# 15P1D_EDA.net
KiCad netlist of a schematic drawn in EasyEDA Pro
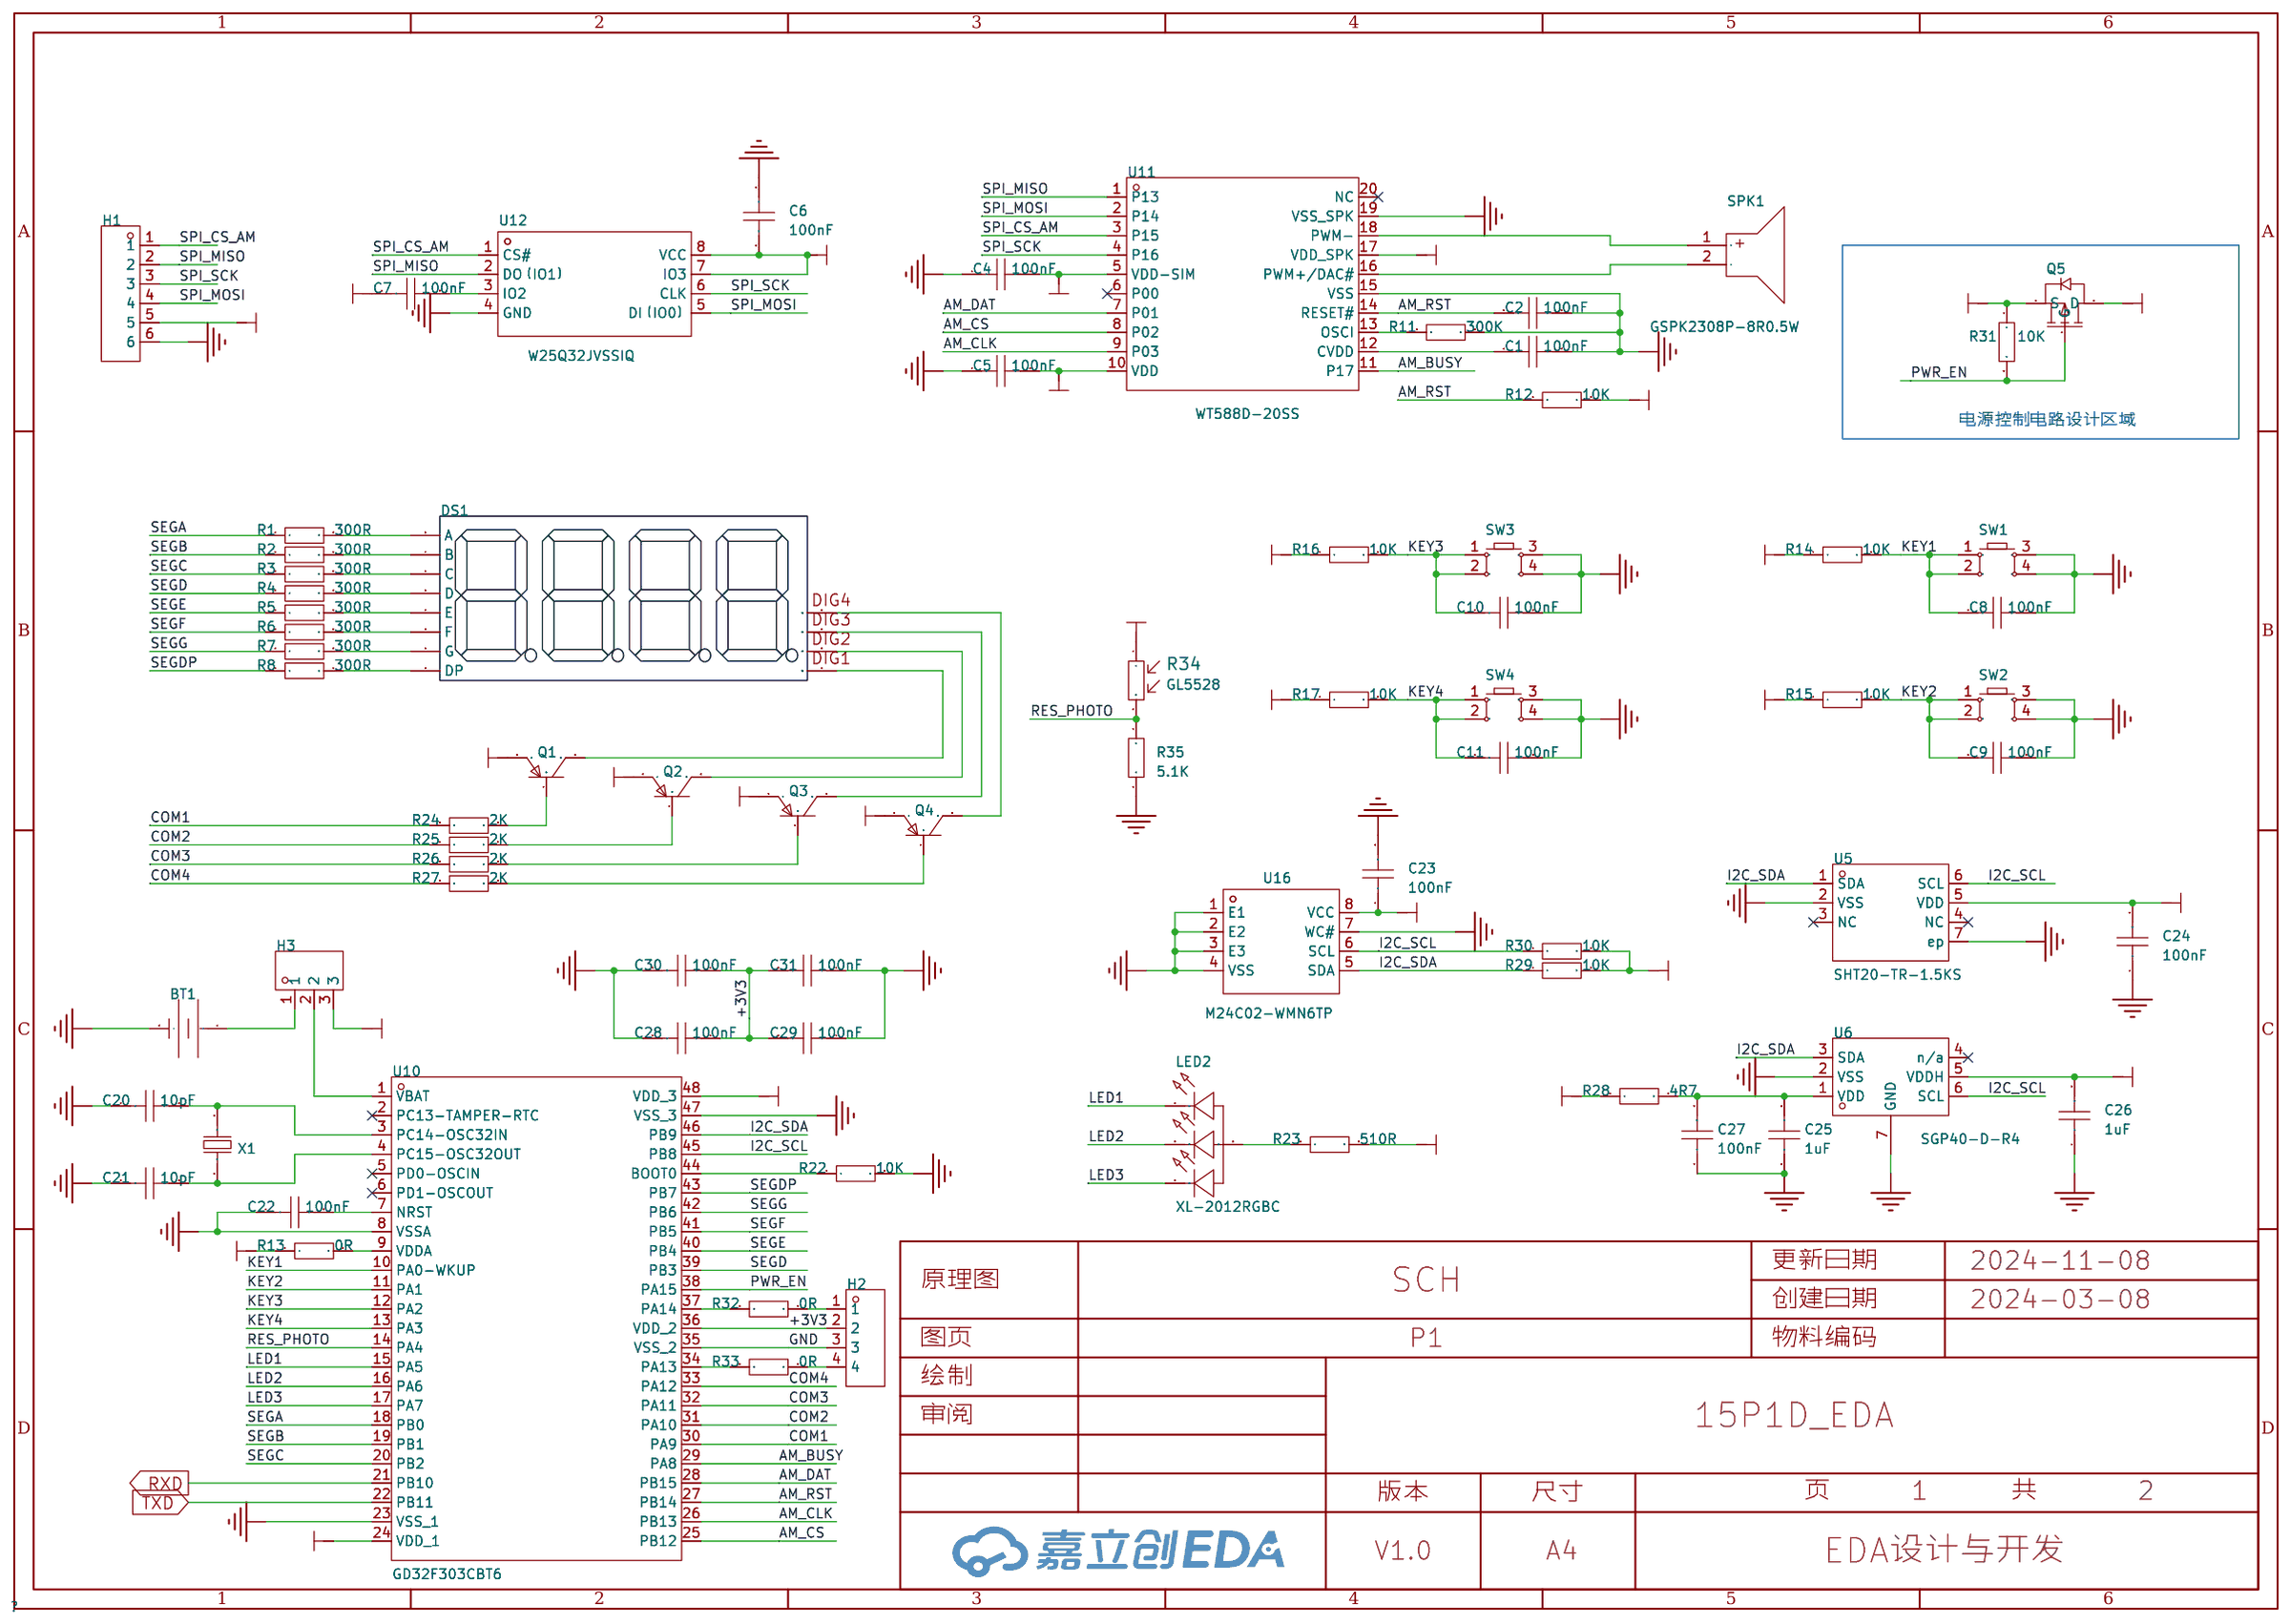
[diagram p0: P1]
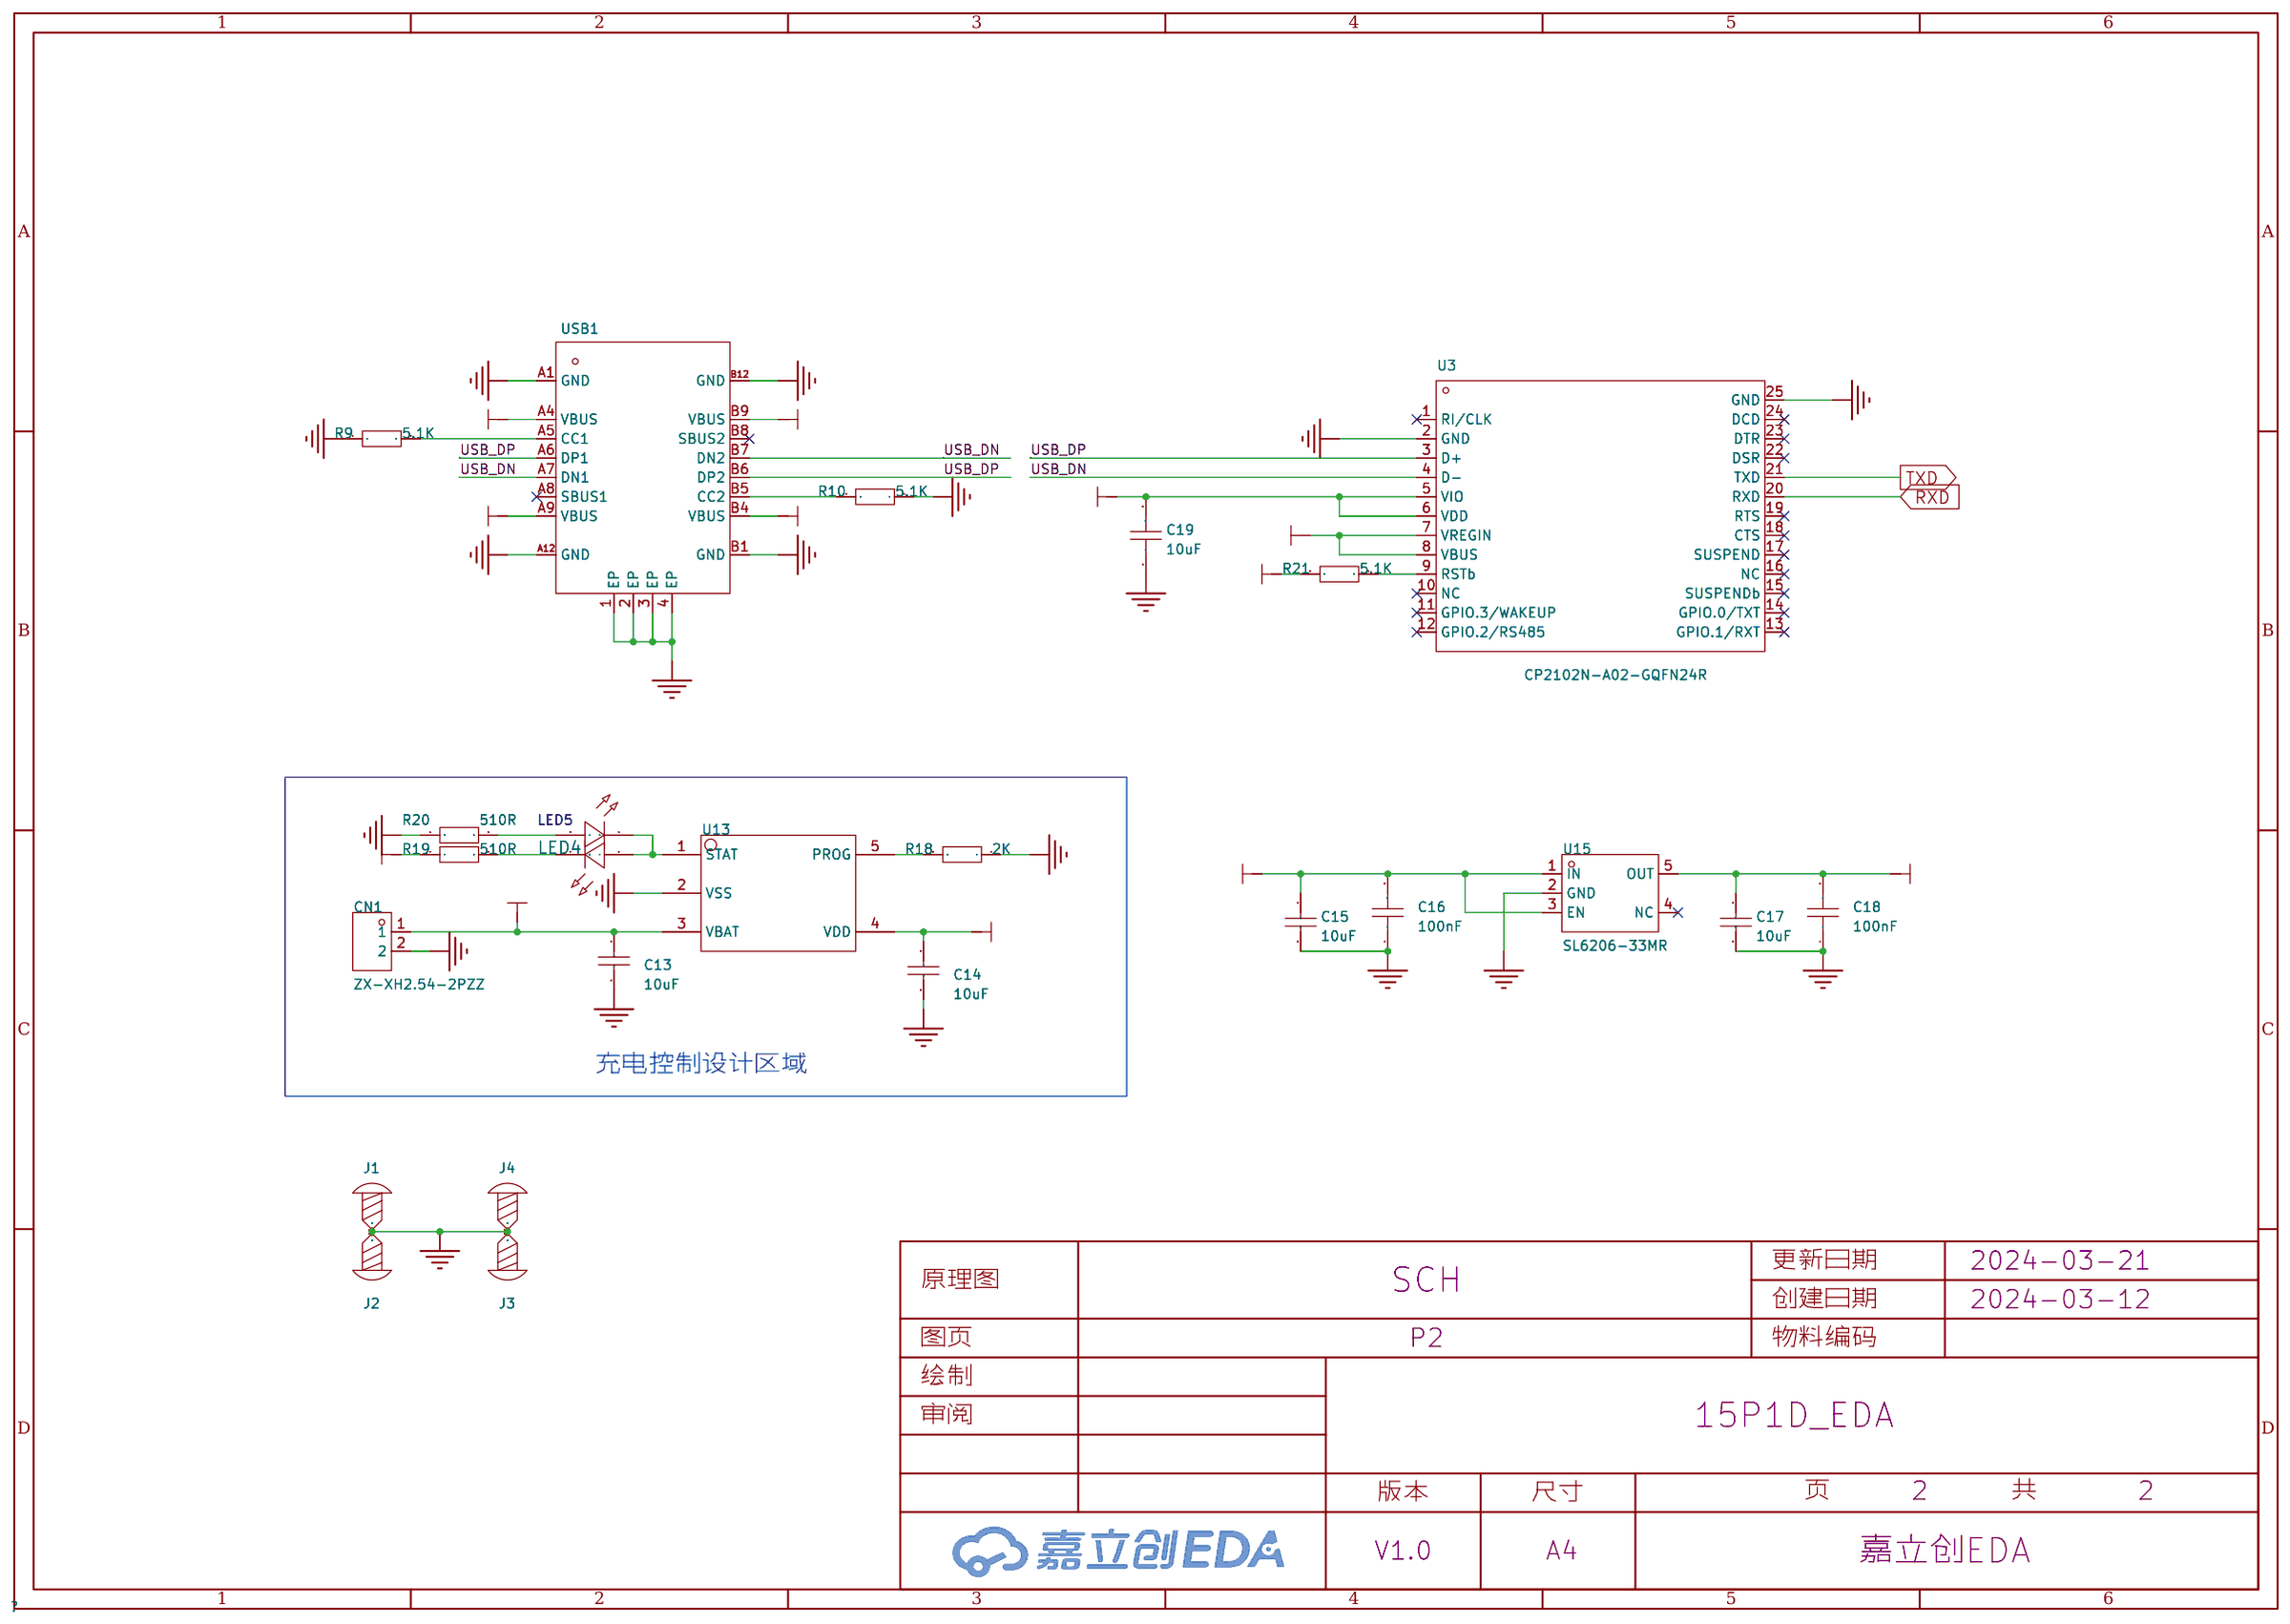
[diagram p1: P2]

(export (version "E")
  (design (tool "Eeschema 10.0.6"))
  (components
    (comp (ref "BT1")
      (value "BS-12-B3AA003")
      (footprint "easyedapro:BAT-SMD_BS-12-B3AA011")
      (description "连接器类型:电池底座;适用电池规格:CR1220;工作温度范围:-25°C~+85°C;")
      (fields (field (name "Manufacturer") "MYOUNG(美阳)"))
      (libsource (lib "easyedapro") (part "BS-12-B3AA003"))
    )
    (comp (ref "C1")
      (value "100nF")
      (footprint "easyedapro:C0805")
      (libsource (lib "easyedapro") (part "CapAcitance"))
    )
    (comp (ref "C2")
      (value "100nF")
      (footprint "easyedapro:C0805")
      (libsource (lib "easyedapro") (part "CapAcitance"))
    )
    (comp (ref "C4")
      (value "100nF")
      (footprint "easyedapro:C0805")
      (libsource (lib "easyedapro") (part "CapAcitance"))
    )
    (comp (ref "C5")
      (value "100nF")
      (footprint "easyedapro:C0805")
      (libsource (lib "easyedapro") (part "CapAcitance"))
    )
    (comp (ref "C6")
      (value "100nF")
      (footprint "easyedapro:C0805")
      (libsource (lib "easyedapro") (part "CapAcitance"))
    )
    (comp (ref "C7")
      (value "100nF")
      (footprint "easyedapro:C0805")
      (libsource (lib "easyedapro") (part "CapAcitance"))
    )
    (comp (ref "C8")
      (value "100nF")
      (footprint "easyedapro:C0805")
      (libsource (lib "easyedapro") (part "CapAcitance"))
    )
    (comp (ref "C9")
      (value "100nF")
      (footprint "easyedapro:C0805")
      (libsource (lib "easyedapro") (part "CapAcitance"))
    )
    (comp (ref "C10")
      (value "100nF")
      (footprint "easyedapro:C0805")
      (libsource (lib "easyedapro") (part "CapAcitance"))
    )
    (comp (ref "C11")
      (value "100nF")
      (footprint "easyedapro:C0805")
      (libsource (lib "easyedapro") (part "CapAcitance"))
    )
    (comp (ref "C20")
      (value "10pF")
      (footprint "easyedapro:C0805")
      (libsource (lib "easyedapro") (part "CapAcitance"))
    )
    (comp (ref "C21")
      (value "10pF")
      (footprint "easyedapro:C0805")
      (libsource (lib "easyedapro") (part "CapAcitance"))
    )
    (comp (ref "C22")
      (value "100nF")
      (footprint "easyedapro:C0805")
      (libsource (lib "easyedapro") (part "CapAcitance"))
    )
    (comp (ref "C23")
      (value "100nF")
      (footprint "easyedapro:C0805")
      (libsource (lib "easyedapro") (part "CapAcitance"))
    )
    (comp (ref "C24")
      (value "100nF")
      (footprint "easyedapro:C0805")
      (libsource (lib "easyedapro") (part "CapAcitance"))
    )
    (comp (ref "C25")
      (value "1uF")
      (footprint "easyedapro:C0805")
      (libsource (lib "easyedapro") (part "CapAcitance"))
    )
    (comp (ref "C26")
      (value "1uF")
      (footprint "easyedapro:C0805")
      (libsource (lib "easyedapro") (part "CapAcitance"))
    )
    (comp (ref "C27")
      (value "100nF")
      (footprint "easyedapro:C0805")
      (libsource (lib "easyedapro") (part "CapAcitance"))
    )
    (comp (ref "C28")
      (value "100nF")
      (footprint "easyedapro:C0805")
      (libsource (lib "easyedapro") (part "CapAcitance"))
    )
    (comp (ref "C29")
      (value "100nF")
      (footprint "easyedapro:C0805")
      (libsource (lib "easyedapro") (part "CapAcitance"))
    )
    (comp (ref "C30")
      (value "100nF")
      (footprint "easyedapro:C0805")
      (libsource (lib "easyedapro") (part "CapAcitance"))
    )
    (comp (ref "C31")
      (value "100nF")
      (footprint "easyedapro:C0805")
      (libsource (lib "easyedapro") (part "CapAcitance"))
    )
    (comp (ref "DS1")
      (value "~")
      (footprint "easyedapro:LED-SEG-TH_FJ5461AH")
      (libsource (lib "easyedapro") (part "LED_SEG_TH_0.56x4"))
    )
    (comp (ref "H1")
      (value "~")
      (footprint "easyedapro:HDR-TH_6P-P2.54-V-F")
      (libsource (lib "easyedapro") (part "Header-Female-2.54_1x6"))
    )
    (comp (ref "H2")
      (value "~")
      (footprint "easyedapro:HDR-TH_4P-P2.54-V-F")
      (libsource (lib "easyedapro") (part "2.54-1*4P母"))
    )
    (comp (ref "H3")
      (value "Jumper3")
      (footprint "easyedapro:HDR-TH_3P-P2.54-V-M-A")
      (libsource (lib "easyedapro") (part "JUMPER3"))
    )
    (comp (ref "LED2")
      (value "XL-2012RGBC")
      (footprint "easyedapro:LED-SMD_4P-L2.0-W1.3-BR")
      (fields (field (name "Manufacturer") "XINGLIGHT(成兴光)"))
      (libsource (lib "easyedapro") (part "XL-2012RGBC"))
    )
    (comp (ref "Q1")
      (value "~")
      (footprint "easyedapro:S8550P_SOT")
      (libsource (lib "easyedapro") (part "PNP"))
    )
    (comp (ref "Q2")
      (value "~")
      (footprint "easyedapro:S8550P_SOT")
      (libsource (lib "easyedapro") (part "PNP"))
    )
    (comp (ref "Q3")
      (value "~")
      (footprint "easyedapro:S8550P_SOT")
      (libsource (lib "easyedapro") (part "PNP"))
    )
    (comp (ref "Q4")
      (value "~")
      (footprint "easyedapro:S8550P_SOT")
      (libsource (lib "easyedapro") (part "PNP"))
    )
    (comp (ref "Q5")
      (value "~")
      (footprint "easyedapro:AO3401A_SOT-23-3")
      (libsource (lib "easyedapro") (part "P_MOS"))
    )
    (comp (ref "R1") (value "300R") (footprint "easyedapro:R0805") (libsource (lib "easyedapro") (part "电阻")))
    (comp (ref "R2") (value "300R") (footprint "easyedapro:R0805") (libsource (lib "easyedapro") (part "电阻")))
    (comp (ref "R3") (value "300R") (footprint "easyedapro:R0805") (libsource (lib "easyedapro") (part "电阻")))
    (comp (ref "R4") (value "300R") (footprint "easyedapro:R0805") (libsource (lib "easyedapro") (part "电阻")))
    (comp (ref "R5") (value "300R") (footprint "easyedapro:R0805") (libsource (lib "easyedapro") (part "电阻")))
    (comp (ref "R6") (value "300R") (footprint "easyedapro:R0805") (libsource (lib "easyedapro") (part "电阻")))
    (comp (ref "R7") (value "300R") (footprint "easyedapro:R0805") (libsource (lib "easyedapro") (part "电阻")))
    (comp (ref "R8") (value "300R") (footprint "easyedapro:R0805") (libsource (lib "easyedapro") (part "电阻")))
    (comp (ref "R11")
      (value "300K")
      (footprint "easyedapro:R0805")
      (libsource (lib "easyedapro") (part "电阻"))
    )
    (comp (ref "R12") (value "10K") (footprint "easyedapro:R0805") (libsource (lib "easyedapro") (part "电阻")))
    (comp (ref "R13") (value "0R") (footprint "easyedapro:R0805") (libsource (lib "easyedapro") (part "电阻")))
    (comp (ref "R14") (value "10K") (footprint "easyedapro:R0805") (libsource (lib "easyedapro") (part "电阻")))
    (comp (ref "R15") (value "10K") (footprint "easyedapro:R0805") (libsource (lib "easyedapro") (part "电阻")))
    (comp (ref "R16") (value "10K") (footprint "easyedapro:R0805") (libsource (lib "easyedapro") (part "电阻")))
    (comp (ref "R17") (value "10K") (footprint "easyedapro:R0805") (libsource (lib "easyedapro") (part "电阻")))
    (comp (ref "R22") (value "10K") (footprint "easyedapro:R0805") (libsource (lib "easyedapro") (part "电阻")))
    (comp (ref "R23")
      (value "510R")
      (footprint "easyedapro:R0805")
      (libsource (lib "easyedapro") (part "电阻"))
    )
    (comp (ref "R24") (value "2K") (footprint "easyedapro:R0805") (libsource (lib "easyedapro") (part "电阻")))
    (comp (ref "R25") (value "2K") (footprint "easyedapro:R0805") (libsource (lib "easyedapro") (part "电阻")))
    (comp (ref "R26") (value "2K") (footprint "easyedapro:R0805") (libsource (lib "easyedapro") (part "电阻")))
    (comp (ref "R27") (value "2K") (footprint "easyedapro:R0805") (libsource (lib "easyedapro") (part "电阻")))
    (comp (ref "R28") (value "4R7") (footprint "easyedapro:R0805") (libsource (lib "easyedapro") (part "电阻")))
    (comp (ref "R29") (value "10K") (footprint "easyedapro:R0805") (libsource (lib "easyedapro") (part "电阻")))
    (comp (ref "R30") (value "10K") (footprint "easyedapro:R0805") (libsource (lib "easyedapro") (part "电阻")))
    (comp (ref "R31") (value "10K") (footprint "easyedapro:R0805") (libsource (lib "easyedapro") (part "电阻")))
    (comp (ref "R32") (value "0R") (footprint "easyedapro:R0805") (libsource (lib "easyedapro") (part "电阻")))
    (comp (ref "R33") (value "0R") (footprint "easyedapro:R0805") (libsource (lib "easyedapro") (part "电阻")))
    (comp (ref "R34")
      (value "GL5528")
      (footprint "easyedapro:RES-TH_L5.1-W4.3-P3.40-D0.5")
      (description "暗电阻:1MΩ;亮电阻 @ 10Lux:8kΩ~20kΩ;光谱峰值(波长):540nm;")
      (fields (field (name "Manufacturer") "森霸"))
      (libsource (lib "easyedapro") (part "GL5528"))
    )
    (comp (ref "R35")
      (value "5.1K")
      (footprint "easyedapro:R0805")
      (libsource (lib "easyedapro") (part "电阻"))
    )
    (comp (ref "SPK1")
      (value "GSPK2308P-8R0.5W")
      (footprint "easyedapro:SPK-TH_BD23.0-P10.00-D0.8-L-RD")
      (fields (field (name "Manufacturer") "INGHAi(赢海)"))
      (libsource (lib "easyedapro") (part "GSPK2308P-8R0.5W"))
    )
    (comp (ref "SW1")
      (value "~")
      (footprint "easyedapro:Key_SMD_12x12x7.3")
      (libsource (lib "easyedapro") (part "轻触按键"))
    )
    (comp (ref "SW2")
      (value "~")
      (footprint "easyedapro:Key_SMD_12x12x7.3")
      (libsource (lib "easyedapro") (part "轻触按键"))
    )
    (comp (ref "SW3")
      (value "~")
      (footprint "easyedapro:Key_SMD_12x12x7.3")
      (libsource (lib "easyedapro") (part "轻触按键"))
    )
    (comp (ref "SW4")
      (value "~")
      (footprint "easyedapro:Key_SMD_12x12x7.3")
      (libsource (lib "easyedapro") (part "轻触按键"))
    )
    (comp (ref "U5")
      (value "SHT20-TR-1.5KS")
      (footprint "easyedapro:DFN-6_L3.0-W3.0-P0.95-TR-EP")
      (description "接口类型:I2C;")
      (fields (field (name "Manufacturer") "Sensirion(瑞士盛思锐)"))
      (libsource (lib "easyedapro") (part "SHT20"))
    )
    (comp (ref "U6")
      (value "SGP40-D-R4")
      (footprint "easyedapro:DFN-6_L2.4-W2.4-P0.80-TL-EP")
      (description "气体类型:空气质量;精度:-;")
      (fields (field (name "Manufacturer") "Sensirion(瑞士盛思锐)"))
      (libsource (lib "easyedapro") (part "SGP40-D-R4"))
    )
    (comp (ref "U10")
      (value "GD32F303CBT6")
      (footprint "easyedapro:LQFP-48_L7.0-W7.0-P0.50-LS9.0-BL")
      (description "CPU内核:CM4;程序存储容量:128KB;RAM总容量:32KB;GPIO端口数量:37;工作电压范围:-;CPU最大主频:120MHz;程序存储器类型:FLASH;")
      (fields (field (name "Manufacturer") "GigaDevice(兆易创新)"))
      (libsource (lib "easyedapro") (part "GD32F303CBT6"))
    )
    (comp (ref "U11")
      (value "WT588D-20SS")
      (footprint "easyedapro:SSOP-20_L7.2-W5.3-P0.65-LS7.8-BL")
      (description "高品质语音芯片")
      (fields (field (name "Manufacturer") "WT(唯创知音)"))
      (libsource (lib "easyedapro") (part "WT588D"))
    )
    (comp (ref "U12")
      (value "W25Q32JVSSIQ")
      (footprint "easyedapro:SOIC-8_L5.3-W5.3-P1.27-LS8.0-BL")
      (description "接口类型:SPI;存储容量:32Mbit;")
      (fields (field (name "Manufacturer") "WINBOND(华邦)"))
      (libsource (lib "easyedapro") (part "W25Q32JVSSIQ"))
    )
    (comp (ref "U16")
      (value "M24C02-WMN6TP")
      (footprint "easyedapro:SOIC-8_L4.9-W3.9-P1.27-LS6.0-BL")
      (description "接口类型:I2C;存储容量:2Kbit;")
      (fields (field (name "Manufacturer") "ST(意法半导体)"))
      (libsource (lib "easyedapro") (part "M24C02-WMN6TP"))
    )
    (comp (ref "X1")
      (value "32.768kHz")
      (footprint "easyedapro:FC-135R_L3.2-W1.5")
      (description "晶振类型:贴片晶振;频率:32.768kHz;常温频差:±20ppm;外接负载电容:12.5pF;")
      (fields (field (name "Manufacturer Part") "Q13FC13500004") (field (name "Manufacturer") "EPSON(爱普生)"))
      (libsource (lib "easyedapro") (part "Q13FC1350000400"))
    )
    (comp (ref "C13")
      (value "10uF")
      (footprint "easyedapro:C1206")
      (description "容值:10uF;精度:±10%;额定电压:50V;材质(温度系数):X5R;")
      (fields
        (field (name "Manufacturer Part") "CL31A106KBHNNNE")
        (field (name "Manufacturer") "SAMSUNG(三星)")
      )
      (libsource (lib "easyedapro") (part "CL31A106KBHNNNE"))
    )
    (comp (ref "C14")
      (value "10uF")
      (footprint "easyedapro:C1206")
      (description "容值:10uF;精度:±10%;额定电压:50V;材质(温度系数):X5R;")
      (fields
        (field (name "Manufacturer Part") "CL31A106KBHNNNE")
        (field (name "Manufacturer") "SAMSUNG(三星)")
      )
      (libsource (lib "easyedapro") (part "CL31A106KBHNNNE"))
    )
    (comp (ref "C15")
      (value "10uF")
      (footprint "easyedapro:C1206")
      (description "容值:10uF;精度:±10%;额定电压:50V;材质(温度系数):X5R;")
      (fields
        (field (name "Manufacturer Part") "CL31A106KBHNNNE")
        (field (name "Manufacturer") "SAMSUNG(三星)")
      )
      (libsource (lib "easyedapro") (part "CL31A106KBHNNNE"))
    )
    (comp (ref "C16")
      (value "100nF")
      (footprint "easyedapro:C0805")
      (libsource (lib "easyedapro") (part "CapAcitance"))
    )
    (comp (ref "C17")
      (value "10uF")
      (footprint "easyedapro:C1206")
      (description "容值:10uF;精度:±10%;额定电压:50V;材质(温度系数):X5R;")
      (fields
        (field (name "Manufacturer Part") "CL31A106KBHNNNE")
        (field (name "Manufacturer") "SAMSUNG(三星)")
      )
      (libsource (lib "easyedapro") (part "CL31A106KBHNNNE"))
    )
    (comp (ref "C18")
      (value "100nF")
      (footprint "easyedapro:C0805")
      (libsource (lib "easyedapro") (part "CapAcitance"))
    )
    (comp (ref "C19")
      (value "10uF")
      (footprint "easyedapro:C0805")
      (libsource (lib "easyedapro") (part "CapAcitance"))
    )
    (comp (ref "CN1")
      (value "ZX-XH2.54-2PZZ")
      (footprint "easyedapro:CONN-TH_2P-P2.50_HX25003-2A")
      (fields (field (name "Manufacturer") "Megastar(兆星)"))
      (libsource (lib "easyedapro") (part "ZX-XH2.54-2PZZ"))
    )
    (comp (ref "J1") (value "~") (footprint "easyedapro:M2螺丝") (libsource (lib "easyedapro") (part "螺丝孔")))
    (comp (ref "J2") (value "~") (footprint "easyedapro:M2螺丝") (libsource (lib "easyedapro") (part "螺丝孔")))
    (comp (ref "J3") (value "~") (footprint "easyedapro:M2螺丝") (libsource (lib "easyedapro") (part "螺丝孔")))
    (comp (ref "J4") (value "~") (footprint "easyedapro:M2螺丝") (libsource (lib "easyedapro") (part "螺丝孔")))
    (comp (ref "LED4")
      (value "~")
      (footprint "easyedapro:LED_0805")
      (libsource (lib "easyedapro") (part "LED_R"))
    )
    (comp (ref "LED5")
      (value "~")
      (footprint "easyedapro:LED_0805")
      (libsource (lib "easyedapro") (part "LED_G"))
    )
    (comp (ref "R9") (value "5.1K") (footprint "easyedapro:R0805") (libsource (lib "easyedapro") (part "电阻")))
    (comp (ref "R10")
      (value "5.1K")
      (footprint "easyedapro:R0805")
      (libsource (lib "easyedapro") (part "电阻"))
    )
    (comp (ref "R18") (value "2K") (footprint "easyedapro:R0805") (libsource (lib "easyedapro") (part "电阻")))
    (comp (ref "R19")
      (value "510R")
      (footprint "easyedapro:R0805")
      (libsource (lib "easyedapro") (part "电阻"))
    )
    (comp (ref "R20")
      (value "510R")
      (footprint "easyedapro:R0805")
      (libsource (lib "easyedapro") (part "电阻"))
    )
    (comp (ref "R21")
      (value "5.1K")
      (footprint "easyedapro:R0805")
      (libsource (lib "easyedapro") (part "电阻"))
    )
    (comp (ref "U3")
      (value "CP2102N-A02-GQFN24R")
      (footprint "easyedapro:QFN-24_L4.0-W4.0-P0.50-TL-EP2.6")
      (description "应用功能:USB转UART;接口协议:UART;")
      (fields (field (name "Manufacturer") "SKYWORKS/SILICON LABS(芯科)"))
      (libsource (lib "easyedapro") (part "CP2102N-A02-GQFN24R"))
    )
    (comp (ref "U13") (value "~") (libsource (lib "easyedapro") (part "BCON")))
    (comp (ref "U15")
      (value "SL6206-33MR")
      (footprint "easyedapro:SOT-23-5_L2.9-W1.6-P0.95-LS2.8-BL")
      (description "输出类型:-;")
      (fields (field (name "Manufacturer") "Slkor(萨科微)"))
      (libsource (lib "easyedapro") (part "SL6206-33MR"))
    )
    (comp (ref "USB1")
      (value "~")
      (footprint "easyedapro:USB_TYPE-C-16P")
      (libsource (lib "easyedapro") (part "USB_TYPE-C-16P"))
    )
  )
  (nets
    (net (code "1") (name "+3V3") (class "Default")
      (node (ref "C17") (pin "2") (pinfunction "2_2") (pintype "input"))
      (node (ref "C18") (pin "2") (pinfunction "2_2") (pintype "input"))
      (node (ref "C19") (pin "2") (pinfunction "2_2") (pintype "input"))
      (node (ref "C23") (pin "1") (pinfunction "1_1") (pintype "input"))
      (node (ref "C28") (pin "1") (pinfunction "1_1") (pintype "input"))
      (node (ref "C29") (pin "2") (pinfunction "2_2") (pintype "input"))
      (node (ref "C30") (pin "1") (pinfunction "1_1") (pintype "input"))
      (node (ref "C31") (pin "2") (pinfunction "2_2") (pintype "input"))
      (node (ref "C4") (pin "2") (pinfunction "2_2") (pintype "input"))
      (node (ref "C5") (pin "2") (pinfunction "2_2") (pintype "input"))
      (node (ref "C6") (pin "2") (pinfunction "2_2") (pintype "input"))
      (node (ref "C7") (pin "1") (pinfunction "1_1") (pintype "input"))
      (node (ref "H1") (pin "5") (pinfunction "5_5") (pintype "unspecified"))
      (node (ref "H2") (pin "2") (pinfunction "2_2") (pintype "unspecified"))
      (node (ref "H3") (pin "3") (pinfunction "3_3") (pintype "input"))
      (node (ref "Q1") (pin "2") (pinfunction "E_2") (pintype "input"))
      (node (ref "Q2") (pin "2") (pinfunction "E_2") (pintype "input"))
      (node (ref "Q3") (pin "2") (pinfunction "E_2") (pintype "input"))
      (node (ref "Q4") (pin "2") (pinfunction "E_2") (pintype "input"))
      (node (ref "Q5") (pin "2") (pinfunction "S_2") (pintype "input"))
      (node (ref "R12") (pin "2") (pinfunction "2_2") (pintype "input"))
      (node (ref "R13") (pin "1") (pinfunction "1_1") (pintype "input"))
      (node (ref "R14") (pin "1") (pinfunction "1_1") (pintype "input"))
      (node (ref "R15") (pin "1") (pinfunction "1_1") (pintype "input"))
      (node (ref "R16") (pin "1") (pinfunction "1_1") (pintype "input"))
      (node (ref "R17") (pin "1") (pinfunction "1_1") (pintype "input"))
      (node (ref "R21") (pin "2") (pinfunction "2_2") (pintype "input"))
      (node (ref "R23") (pin "2") (pinfunction "2_2") (pintype "input"))
      (node (ref "R29") (pin "2") (pinfunction "2_2") (pintype "input"))
      (node (ref "R30") (pin "2") (pinfunction "2_2") (pintype "input"))
      (node (ref "R31") (pin "1") (pinfunction "1_1") (pintype "input"))
      (node (ref "R34") (pin "1") (pinfunction "1_1") (pintype "input"))
      (node (ref "U10") (pin "24") (pinfunction "VDD_1_24") (pintype "unspecified"))
      (node (ref "U10") (pin "36") (pinfunction "VDD_2_36") (pintype "unspecified"))
      (node (ref "U10") (pin "48") (pinfunction "VDD_3_48") (pintype "unspecified"))
      (node (ref "U11") (pin "10") (pinfunction "VDD_10") (pintype "input"))
      (node (ref "U11") (pin "17") (pinfunction "VDD_SPK_17") (pintype "input"))
      (node (ref "U11") (pin "5") (pinfunction "VDD-SIM_5") (pintype "input"))
      (node (ref "U12") (pin "7") (pinfunction "IO3_7") (pintype "unspecified"))
      (node (ref "U12") (pin "8") (pinfunction "VCC_8") (pintype "unspecified"))
      (node (ref "U15") (pin "5") (pinfunction "OUT_5") (pintype "unspecified"))
      (node (ref "U16") (pin "8") (pinfunction "VCC_8") (pintype "unspecified"))
      (node (ref "U3") (pin "5") (pinfunction "VIO_5") (pintype "unspecified"))
      (node (ref "U3") (pin "6") (pinfunction "VDD_6") (pintype "unspecified"))
    )
    (net (code "2") (name "+VS") (class "Default")
      (node (ref "C24") (pin "2") (pinfunction "2_2") (pintype "input"))
      (node (ref "C26") (pin "2") (pinfunction "2_2") (pintype "input"))
      (node (ref "Q5") (pin "3") (pinfunction "D_3") (pintype "input"))
      (node (ref "R28") (pin "1") (pinfunction "1_1") (pintype "input"))
      (node (ref "U5") (pin "5") (pinfunction "VDD_5") (pintype "unspecified"))
      (node (ref "U6") (pin "5") (pinfunction "VDDH_5") (pintype "unspecified"))
    )
    (net (code "3") (name "AM_BUSY") (class "Default")
      (node (ref "U10") (pin "29") (pinfunction "PA8_29") (pintype "unspecified"))
      (node (ref "U11") (pin "11") (pinfunction "P17_11") (pintype "input"))
    )
    (net (code "4") (name "AM_CLK") (class "Default")
      (node (ref "U10") (pin "26") (pinfunction "PB13_26") (pintype "unspecified"))
      (node (ref "U11") (pin "9") (pinfunction "P03_9") (pintype "input"))
    )
    (net (code "5") (name "AM_CS") (class "Default")
      (node (ref "U10") (pin "25") (pinfunction "PB12_25") (pintype "unspecified"))
      (node (ref "U11") (pin "8") (pinfunction "P02_8") (pintype "input"))
    )
    (net (code "6") (name "AM_DAT") (class "Default")
      (node (ref "U10") (pin "28") (pinfunction "PB15_28") (pintype "unspecified"))
      (node (ref "U11") (pin "7") (pinfunction "P01_7") (pintype "input"))
    )
    (net (code "7") (name "AM_RST") (class "Default")
      (node (ref "C2") (pin "1") (pinfunction "1_1") (pintype "input"))
      (node (ref "R12") (pin "1") (pinfunction "1_1") (pintype "input"))
      (node (ref "U10") (pin "27") (pinfunction "PB14_27") (pintype "unspecified"))
      (node (ref "U11") (pin "14") (pinfunction "RESET#_14") (pintype "input"))
    )
    (net (code "8") (name "COM1") (class "Default")
      (node (ref "R24") (pin "1") (pinfunction "1_1") (pintype "input"))
      (node (ref "U10") (pin "30") (pinfunction "PA9_30") (pintype "unspecified"))
    )
    (net (code "9") (name "COM2") (class "Default")
      (node (ref "R25") (pin "1") (pinfunction "1_1") (pintype "input"))
      (node (ref "U10") (pin "31") (pinfunction "PA10_31") (pintype "unspecified"))
    )
    (net (code "10") (name "COM3") (class "Default")
      (node (ref "R26") (pin "1") (pinfunction "1_1") (pintype "input"))
      (node (ref "U10") (pin "32") (pinfunction "PA11_32") (pintype "unspecified"))
    )
    (net (code "11") (name "COM4") (class "Default")
      (node (ref "R27") (pin "1") (pinfunction "1_1") (pintype "input"))
      (node (ref "U10") (pin "33") (pinfunction "PA12_33") (pintype "unspecified"))
    )
    (net (code "12") (name "GND") (class "Default")
      (node (ref "BT1") (pin "2") (pinfunction "-_2") (pintype "unspecified"))
      (node (ref "C1") (pin "2") (pinfunction "2_2") (pintype "input"))
      (node (ref "C10") (pin "2") (pinfunction "2_2") (pintype "input"))
      (node (ref "C11") (pin "2") (pinfunction "2_2") (pintype "input"))
      (node (ref "C13") (pin "2") (pinfunction "2_2") (pintype "input"))
      (node (ref "C14") (pin "1") (pinfunction "1_1") (pintype "input"))
      (node (ref "C15") (pin "1") (pinfunction "1_1") (pintype "input"))
      (node (ref "C16") (pin "1") (pinfunction "1_1") (pintype "input"))
      (node (ref "C17") (pin "1") (pinfunction "1_1") (pintype "input"))
      (node (ref "C18") (pin "1") (pinfunction "1_1") (pintype "input"))
      (node (ref "C19") (pin "1") (pinfunction "1_1") (pintype "input"))
      (node (ref "C2") (pin "2") (pinfunction "2_2") (pintype "input"))
      (node (ref "C20") (pin "1") (pinfunction "1_1") (pintype "input"))
      (node (ref "C21") (pin "1") (pinfunction "1_1") (pintype "input"))
      (node (ref "C22") (pin "1") (pinfunction "1_1") (pintype "input"))
      (node (ref "C23") (pin "2") (pinfunction "2_2") (pintype "input"))
      (node (ref "C24") (pin "1") (pinfunction "1_1") (pintype "input"))
      (node (ref "C25") (pin "1") (pinfunction "1_1") (pintype "input"))
      (node (ref "C26") (pin "1") (pinfunction "1_1") (pintype "input"))
      (node (ref "C27") (pin "1") (pinfunction "1_1") (pintype "input"))
      (node (ref "C28") (pin "2") (pinfunction "2_2") (pintype "input"))
      (node (ref "C29") (pin "1") (pinfunction "1_1") (pintype "input"))
      (node (ref "C30") (pin "2") (pinfunction "2_2") (pintype "input"))
      (node (ref "C31") (pin "1") (pinfunction "1_1") (pintype "input"))
      (node (ref "C4") (pin "1") (pinfunction "1_1") (pintype "input"))
      (node (ref "C5") (pin "1") (pinfunction "1_1") (pintype "input"))
      (node (ref "C6") (pin "1") (pinfunction "1_1") (pintype "input"))
      (node (ref "C8") (pin "2") (pinfunction "2_2") (pintype "input"))
      (node (ref "C9") (pin "2") (pinfunction "2_2") (pintype "input"))
      (node (ref "CN1") (pin "2") (pinfunction "2_2") (pintype "unspecified"))
      (node (ref "H1") (pin "6") (pinfunction "6_6") (pintype "unspecified"))
      (node (ref "H2") (pin "3") (pinfunction "3_3") (pintype "unspecified"))
      (node (ref "J1") (pin "1") (pinfunction "1_1") (pintype "input"))
      (node (ref "J2") (pin "1") (pinfunction "1_1") (pintype "input"))
      (node (ref "J3") (pin "1") (pinfunction "1_1") (pintype "input"))
      (node (ref "J4") (pin "1") (pinfunction "1_1") (pintype "input"))
      (node (ref "R10") (pin "1") (pinfunction "1_1") (pintype "input"))
      (node (ref "R11") (pin "2") (pinfunction "2_2") (pintype "input"))
      (node (ref "R18") (pin "1") (pinfunction "1_1") (pintype "input"))
      (node (ref "R20") (pin "1") (pinfunction "1_1") (pintype "input"))
      (node (ref "R22") (pin "2") (pinfunction "2_2") (pintype "input"))
      (node (ref "R35") (pin "2") (pinfunction "2_2") (pintype "input"))
      (node (ref "R9") (pin "1") (pinfunction "1_1") (pintype "input"))
      (node (ref "SW1") (pin "3") (pinfunction "3_3") (pintype "input"))
      (node (ref "SW1") (pin "4") (pinfunction "4_4") (pintype "input"))
      (node (ref "SW2") (pin "3") (pinfunction "3_3") (pintype "input"))
      (node (ref "SW2") (pin "4") (pinfunction "4_4") (pintype "input"))
      (node (ref "SW3") (pin "3") (pinfunction "3_3") (pintype "input"))
      (node (ref "SW3") (pin "4") (pinfunction "4_4") (pintype "input"))
      (node (ref "SW4") (pin "3") (pinfunction "3_3") (pintype "input"))
      (node (ref "SW4") (pin "4") (pinfunction "4_4") (pintype "input"))
      (node (ref "U10") (pin "23") (pinfunction "VSS_1_23") (pintype "unspecified"))
      (node (ref "U10") (pin "35") (pinfunction "VSS_2_35") (pintype "unspecified"))
      (node (ref "U10") (pin "47") (pinfunction "VSS_3_47") (pintype "unspecified"))
      (node (ref "U10") (pin "8") (pinfunction "VSSA_8") (pintype "unspecified"))
      (node (ref "U11") (pin "15") (pinfunction "VSS_15") (pintype "input"))
      (node (ref "U11") (pin "19") (pinfunction "VSS_SPK_19") (pintype "input"))
      (node (ref "U12") (pin "4") (pinfunction "GND_4") (pintype "unspecified"))
      (node (ref "U13") (pin "2") (pinfunction "VSS_2") (pintype "input"))
      (node (ref "U15") (pin "2") (pinfunction "GND_2") (pintype "unspecified"))
      (node (ref "U16") (pin "1") (pinfunction "E1_1") (pintype "unspecified"))
      (node (ref "U16") (pin "2") (pinfunction "E2_2") (pintype "unspecified"))
      (node (ref "U16") (pin "3") (pinfunction "E3_3") (pintype "unspecified"))
      (node (ref "U16") (pin "4") (pinfunction "VSS_4") (pintype "unspecified"))
      (node (ref "U16") (pin "7") (pinfunction "WC#_7") (pintype "unspecified"))
      (node (ref "U3") (pin "2") (pinfunction "GND_2") (pintype "unspecified"))
      (node (ref "U3") (pin "25") (pinfunction "GND_25") (pintype "unspecified"))
      (node (ref "U5") (pin "2") (pinfunction "VSS_2") (pintype "unspecified"))
      (node (ref "U5") (pin "7") (pinfunction "ep_7") (pintype "unspecified"))
      (node (ref "U6") (pin "2") (pinfunction "VSS_2") (pintype "unspecified"))
      (node (ref "U6") (pin "7") (pinfunction "GND_7") (pintype "unspecified"))
      (node (ref "USB1") (pin "1") (pinfunction "EP_1") (pintype "input"))
      (node (ref "USB1") (pin "2") (pinfunction "EP_2") (pintype "input"))
      (node (ref "USB1") (pin "3") (pinfunction "EP_3") (pintype "input"))
      (node (ref "USB1") (pin "4") (pinfunction "EP_4") (pintype "input"))
      (node (ref "USB1") (pin "A1") (pinfunction "GND_A1") (pintype "input"))
      (node (ref "USB1") (pin "A12") (pinfunction "GND_A12") (pintype "input"))
      (node (ref "USB1") (pin "B1") (pinfunction "GND_B1") (pintype "input"))
      (node (ref "USB1") (pin "B12") (pinfunction "GND_B12") (pintype "input"))
    )
    (net (code "13") (name "I2C_SCL") (class "Default")
      (node (ref "R30") (pin "1") (pinfunction "1_1") (pintype "input"))
      (node (ref "U10") (pin "45") (pinfunction "PB8_45") (pintype "unspecified"))
      (node (ref "U16") (pin "6") (pinfunction "SCL_6") (pintype "unspecified"))
      (node (ref "U5") (pin "6") (pinfunction "SCL_6") (pintype "unspecified"))
      (node (ref "U6") (pin "6") (pinfunction "SCL_6") (pintype "unspecified"))
    )
    (net (code "14") (name "I2C_SDA") (class "Default")
      (node (ref "R29") (pin "1") (pinfunction "1_1") (pintype "input"))
      (node (ref "U10") (pin "46") (pinfunction "PB9_46") (pintype "unspecified"))
      (node (ref "U16") (pin "5") (pinfunction "SDA_5") (pintype "unspecified"))
      (node (ref "U5") (pin "1") (pinfunction "SDA_1") (pintype "unspecified"))
      (node (ref "U6") (pin "3") (pinfunction "SDA_3") (pintype "unspecified"))
    )
    (net (code "15") (name "KEY1") (class "Default")
      (node (ref "C8") (pin "1") (pinfunction "1_1") (pintype "input"))
      (node (ref "R14") (pin "2") (pinfunction "2_2") (pintype "input"))
      (node (ref "SW1") (pin "1") (pinfunction "1_1") (pintype "input"))
      (node (ref "SW1") (pin "2") (pinfunction "2_2") (pintype "input"))
      (node (ref "U10") (pin "10") (pinfunction "PA0-WKUP_10") (pintype "unspecified"))
    )
    (net (code "16") (name "KEY2") (class "Default")
      (node (ref "C9") (pin "1") (pinfunction "1_1") (pintype "input"))
      (node (ref "R15") (pin "2") (pinfunction "2_2") (pintype "input"))
      (node (ref "SW2") (pin "1") (pinfunction "1_1") (pintype "input"))
      (node (ref "SW2") (pin "2") (pinfunction "2_2") (pintype "input"))
      (node (ref "U10") (pin "11") (pinfunction "PA1_11") (pintype "unspecified"))
    )
    (net (code "17") (name "KEY3") (class "Default")
      (node (ref "C10") (pin "1") (pinfunction "1_1") (pintype "input"))
      (node (ref "R16") (pin "2") (pinfunction "2_2") (pintype "input"))
      (node (ref "SW3") (pin "1") (pinfunction "1_1") (pintype "input"))
      (node (ref "SW3") (pin "2") (pinfunction "2_2") (pintype "input"))
      (node (ref "U10") (pin "12") (pinfunction "PA2_12") (pintype "unspecified"))
    )
    (net (code "18") (name "KEY4") (class "Default")
      (node (ref "C11") (pin "1") (pinfunction "1_1") (pintype "input"))
      (node (ref "R17") (pin "2") (pinfunction "2_2") (pintype "input"))
      (node (ref "SW4") (pin "1") (pinfunction "1_1") (pintype "input"))
      (node (ref "SW4") (pin "2") (pinfunction "2_2") (pintype "input"))
      (node (ref "U10") (pin "13") (pinfunction "PA3_13") (pintype "unspecified"))
    )
    (net (code "19") (name "LED1") (class "Default")
      (node (ref "LED2") (pin "1") (pinfunction "1_1") (pintype "unspecified"))
      (node (ref "U10") (pin "15") (pinfunction "PA5_15") (pintype "unspecified"))
    )
    (net (code "20") (name "LED2") (class "Default")
      (node (ref "LED2") (pin "2") (pinfunction "2_2") (pintype "unspecified"))
      (node (ref "U10") (pin "16") (pinfunction "PA6_16") (pintype "unspecified"))
    )
    (net (code "21") (name "LED3") (class "Default")
      (node (ref "LED2") (pin "4") (pinfunction "4_4") (pintype "unspecified"))
      (node (ref "U10") (pin "17") (pinfunction "PA7_17") (pintype "unspecified"))
    )
    (net (code "22") (name "Net-(BT1-+)") (class "Default")
      (node (ref "BT1") (pin "1") (pinfunction "+_1") (pintype "unspecified"))
      (node (ref "H3") (pin "1") (pinfunction "1_1") (pintype "input"))
    )
    (net (code "23") (name "Net-(DS1-A)") (class "Default")
      (node (ref "DS1") (pin "11") (pinfunction "A_11") (pintype "input"))
      (node (ref "R1") (pin "2") (pinfunction "2_2") (pintype "input"))
    )
    (net (code "24") (name "Net-(DS1-B)") (class "Default")
      (node (ref "DS1") (pin "7") (pinfunction "B_7") (pintype "input"))
      (node (ref "R2") (pin "2") (pinfunction "2_2") (pintype "input"))
    )
    (net (code "25") (name "Net-(DS1-C)") (class "Default")
      (node (ref "DS1") (pin "4") (pinfunction "C_4") (pintype "input"))
      (node (ref "R3") (pin "2") (pinfunction "2_2") (pintype "input"))
    )
    (net (code "26") (name "Net-(DS1-D)") (class "Default")
      (node (ref "DS1") (pin "2") (pinfunction "D_2") (pintype "input"))
      (node (ref "R4") (pin "2") (pinfunction "2_2") (pintype "input"))
    )
    (net (code "27") (name "Net-(DS1-DIG1)") (class "Default")
      (node (ref "DS1") (pin "12") (pinfunction "DIG1_12") (pintype "input"))
      (node (ref "Q1") (pin "3") (pinfunction "C_3") (pintype "input"))
    )
    (net (code "28") (name "Net-(DS1-DIG2)") (class "Default")
      (node (ref "DS1") (pin "9") (pinfunction "DIG2_9") (pintype "input"))
      (node (ref "Q2") (pin "3") (pinfunction "C_3") (pintype "input"))
    )
    (net (code "29") (name "Net-(DS1-DIG3)") (class "Default")
      (node (ref "DS1") (pin "8") (pinfunction "DIG3_8") (pintype "input"))
      (node (ref "Q3") (pin "3") (pinfunction "C_3") (pintype "input"))
    )
    (net (code "30") (name "Net-(DS1-DIG4)") (class "Default")
      (node (ref "DS1") (pin "6") (pinfunction "DIG4_6") (pintype "input"))
      (node (ref "Q4") (pin "3") (pinfunction "C_3") (pintype "input"))
    )
    (net (code "31") (name "Net-(DS1-DP)") (class "Default")
      (node (ref "DS1") (pin "3") (pinfunction "DP_3") (pintype "input"))
      (node (ref "R8") (pin "2") (pinfunction "2_2") (pintype "input"))
    )
    (net (code "32") (name "Net-(DS1-E)") (class "Default")
      (node (ref "DS1") (pin "1") (pinfunction "E_1") (pintype "input"))
      (node (ref "R5") (pin "2") (pinfunction "2_2") (pintype "input"))
    )
    (net (code "33") (name "Net-(DS1-F)") (class "Default")
      (node (ref "DS1") (pin "10") (pinfunction "F_10") (pintype "input"))
      (node (ref "R6") (pin "2") (pinfunction "2_2") (pintype "input"))
    )
    (net (code "34") (name "Net-(DS1-G)") (class "Default")
      (node (ref "DS1") (pin "5") (pinfunction "G_5") (pintype "input"))
      (node (ref "R7") (pin "2") (pinfunction "2_2") (pintype "input"))
    )
    (net (code "35") (name "Net-(H2-Pad1)") (class "Default")
      (node (ref "H2") (pin "1") (pinfunction "1_1") (pintype "unspecified"))
      (node (ref "R32") (pin "2") (pinfunction "2_2") (pintype "input"))
    )
    (net (code "36") (name "Net-(H2-Pad4)") (class "Default")
      (node (ref "H2") (pin "4") (pinfunction "4_4") (pintype "unspecified"))
      (node (ref "R33") (pin "2") (pinfunction "2_2") (pintype "input"))
    )
    (net (code "37") (name "Net-(LED2-Pad3)") (class "Default")
      (node (ref "LED2") (pin "3") (pinfunction "3_3") (pintype "unspecified"))
      (node (ref "R23") (pin "1") (pinfunction "1_1") (pintype "input"))
    )
    (net (code "38") (name "Net-(LED4-A)") (class "Default")
      (node (ref "LED4") (pin "2") (pinfunction "A_2") (pintype "input"))
      (node (ref "LED5") (pin "1") (pinfunction "C_1") (pintype "input"))
      (node (ref "U13") (pin "1") (pinfunction "STAT_1") (pintype "input"))
    )
    (net (code "39") (name "Net-(LED4-C)") (class "Default")
      (node (ref "LED4") (pin "1") (pinfunction "C_1") (pintype "input"))
      (node (ref "R19") (pin "2") (pinfunction "2_2") (pintype "input"))
    )
    (net (code "40") (name "Net-(LED5-A)") (class "Default")
      (node (ref "LED5") (pin "2") (pinfunction "A_2") (pintype "input"))
      (node (ref "R20") (pin "2") (pinfunction "2_2") (pintype "input"))
    )
    (net (code "41") (name "Net-(Q1-B)") (class "Default")
      (node (ref "Q1") (pin "1") (pinfunction "B_1") (pintype "input"))
      (node (ref "R24") (pin "2") (pinfunction "2_2") (pintype "input"))
    )
    (net (code "42") (name "Net-(Q2-B)") (class "Default")
      (node (ref "Q2") (pin "1") (pinfunction "B_1") (pintype "input"))
      (node (ref "R25") (pin "2") (pinfunction "2_2") (pintype "input"))
    )
    (net (code "43") (name "Net-(Q3-B)") (class "Default")
      (node (ref "Q3") (pin "1") (pinfunction "B_1") (pintype "input"))
      (node (ref "R26") (pin "2") (pinfunction "2_2") (pintype "input"))
    )
    (net (code "44") (name "Net-(Q4-B)") (class "Default")
      (node (ref "Q4") (pin "1") (pinfunction "B_1") (pintype "input"))
      (node (ref "R27") (pin "2") (pinfunction "2_2") (pintype "input"))
    )
    (net (code "45") (name "Net-(SPK1-+)") (class "Default")
      (node (ref "SPK1") (pin "1") (pinfunction "+_1") (pintype "input"))
      (node (ref "U11") (pin "18") (pinfunction "PWM-_18") (pintype "input"))
    )
    (net (code "46") (name "Net-(SPK1--)") (class "Default")
      (node (ref "SPK1") (pin "2") (pinfunction "-_2") (pintype "input"))
      (node (ref "U11") (pin "16") (pinfunction "PWM+/DAC#_16") (pintype "input"))
    )
    (net (code "47") (name "Net-(U3-RSTb)") (class "Default")
      (node (ref "R21") (pin "1") (pinfunction "1_1") (pintype "input"))
      (node (ref "U3") (pin "9") (pinfunction "RSTb_9") (pintype "unspecified"))
    )
    (net (code "48") (name "Net-(U6-VDD)") (class "Default")
      (node (ref "C25") (pin "2") (pinfunction "2_2") (pintype "input"))
      (node (ref "C27") (pin "2") (pinfunction "2_2") (pintype "input"))
      (node (ref "R28") (pin "2") (pinfunction "2_2") (pintype "input"))
      (node (ref "U6") (pin "1") (pinfunction "VDD_1") (pintype "unspecified"))
    )
    (net (code "49") (name "Net-(U10-BOOT0)") (class "Default")
      (node (ref "R22") (pin "1") (pinfunction "1_1") (pintype "input"))
      (node (ref "U10") (pin "44") (pinfunction "BOOT0_44") (pintype "unspecified"))
    )
    (net (code "50") (name "Net-(U10-NRST)") (class "Default")
      (node (ref "C22") (pin "2") (pinfunction "2_2") (pintype "input"))
      (node (ref "U10") (pin "7") (pinfunction "NRST_7") (pintype "unspecified"))
    )
    (net (code "51") (name "Net-(U10-PA13)") (class "Default")
      (node (ref "R33") (pin "1") (pinfunction "1_1") (pintype "input"))
      (node (ref "U10") (pin "34") (pinfunction "PA13_34") (pintype "unspecified"))
    )
    (net (code "52") (name "Net-(U10-PA14)") (class "Default")
      (node (ref "R32") (pin "1") (pinfunction "1_1") (pintype "input"))
      (node (ref "U10") (pin "37") (pinfunction "PA14_37") (pintype "unspecified"))
    )
    (net (code "53") (name "Net-(U10-PC14-OSC32IN)") (class "Default")
      (node (ref "C20") (pin "2") (pinfunction "2_2") (pintype "input"))
      (node (ref "U10") (pin "3") (pinfunction "PC14-OSC32IN_3") (pintype "unspecified"))
      (node (ref "X1") (pin "1") (pinfunction "1_1") (pintype "unspecified"))
    )
    (net (code "54") (name "Net-(U10-PC15-OSC32OUT)") (class "Default")
      (node (ref "C21") (pin "2") (pinfunction "2_2") (pintype "input"))
      (node (ref "U10") (pin "4") (pinfunction "PC15-OSC32OUT_4") (pintype "unspecified"))
      (node (ref "X1") (pin "2") (pinfunction "2_2") (pintype "unspecified"))
    )
    (net (code "55") (name "Net-(U10-VBAT)") (class "Default")
      (node (ref "H3") (pin "2") (pinfunction "2_2") (pintype "input"))
      (node (ref "U10") (pin "1") (pinfunction "VBAT_1") (pintype "unspecified"))
    )
    (net (code "56") (name "Net-(U10-VDDA)") (class "Default")
      (node (ref "R13") (pin "2") (pinfunction "2_2") (pintype "input"))
      (node (ref "U10") (pin "9") (pinfunction "VDDA_9") (pintype "unspecified"))
    )
    (net (code "57") (name "Net-(U11-CVDD)") (class "Default")
      (node (ref "C1") (pin "1") (pinfunction "1_1") (pintype "input"))
      (node (ref "U11") (pin "12") (pinfunction "CVDD_12") (pintype "input"))
    )
    (net (code "58") (name "Net-(U11-OSCI)") (class "Default")
      (node (ref "R11") (pin "1") (pinfunction "1_1") (pintype "input"))
      (node (ref "U11") (pin "13") (pinfunction "OSCI_13") (pintype "input"))
    )
    (net (code "59") (name "Net-(U12-IO2)") (class "Default")
      (node (ref "C7") (pin "2") (pinfunction "2_2") (pintype "input"))
      (node (ref "U12") (pin "3") (pinfunction "IO2_3") (pintype "unspecified"))
    )
    (net (code "60") (name "Net-(U13-PROG)") (class "Default")
      (node (ref "R18") (pin "2") (pinfunction "2_2") (pintype "input"))
      (node (ref "U13") (pin "5") (pinfunction "PROG_5") (pintype "input"))
    )
    (net (code "61") (name "Net-(USB1-CC1)") (class "Default")
      (node (ref "R9") (pin "2") (pinfunction "2_2") (pintype "input"))
      (node (ref "USB1") (pin "A5") (pinfunction "CC1_A5") (pintype "input"))
    )
    (net (code "62") (name "Net-(USB1-CC2)") (class "Default")
      (node (ref "R10") (pin "2") (pinfunction "2_2") (pintype "input"))
      (node (ref "USB1") (pin "B5") (pinfunction "CC2_B5") (pintype "input"))
    )
    (net (code "63") (name "PWR_EN") (class "Default")
      (node (ref "Q5") (pin "1") (pinfunction "G_1") (pintype "input"))
      (node (ref "R31") (pin "2") (pinfunction "2_2") (pintype "input"))
      (node (ref "U10") (pin "38") (pinfunction "PA15_38") (pintype "unspecified"))
    )
    (net (code "64") (name "RES_PHOTO") (class "Default")
      (node (ref "R34") (pin "2") (pinfunction "2_2") (pintype "input"))
      (node (ref "R35") (pin "1") (pinfunction "1_1") (pintype "input"))
      (node (ref "U10") (pin "14") (pinfunction "PA4_14") (pintype "unspecified"))
    )
    (net (code "65") (name "RXD") (class "Default")
      (node (ref "U10") (pin "21") (pinfunction "PB10_21") (pintype "unspecified"))
      (node (ref "U3") (pin "20") (pinfunction "RXD_20") (pintype "unspecified"))
    )
    (net (code "66") (name "SEGA") (class "Default")
      (node (ref "R1") (pin "1") (pinfunction "1_1") (pintype "input"))
      (node (ref "U10") (pin "18") (pinfunction "PB0_18") (pintype "unspecified"))
    )
    (net (code "67") (name "SEGB") (class "Default")
      (node (ref "R2") (pin "1") (pinfunction "1_1") (pintype "input"))
      (node (ref "U10") (pin "19") (pinfunction "PB1_19") (pintype "unspecified"))
    )
    (net (code "68") (name "SEGC") (class "Default")
      (node (ref "R3") (pin "1") (pinfunction "1_1") (pintype "input"))
      (node (ref "U10") (pin "20") (pinfunction "PB2_20") (pintype "unspecified"))
    )
    (net (code "69") (name "SEGD") (class "Default")
      (node (ref "R4") (pin "1") (pinfunction "1_1") (pintype "input"))
      (node (ref "U10") (pin "39") (pinfunction "PB3_39") (pintype "unspecified"))
    )
    (net (code "70") (name "SEGDP") (class "Default")
      (node (ref "R8") (pin "1") (pinfunction "1_1") (pintype "input"))
      (node (ref "U10") (pin "43") (pinfunction "PB7_43") (pintype "unspecified"))
    )
    (net (code "71") (name "SEGE") (class "Default")
      (node (ref "R5") (pin "1") (pinfunction "1_1") (pintype "input"))
      (node (ref "U10") (pin "40") (pinfunction "PB4_40") (pintype "unspecified"))
    )
    (net (code "72") (name "SEGF") (class "Default")
      (node (ref "R6") (pin "1") (pinfunction "1_1") (pintype "input"))
      (node (ref "U10") (pin "41") (pinfunction "PB5_41") (pintype "unspecified"))
    )
    (net (code "73") (name "SEGG") (class "Default")
      (node (ref "R7") (pin "1") (pinfunction "1_1") (pintype "input"))
      (node (ref "U10") (pin "42") (pinfunction "PB6_42") (pintype "unspecified"))
    )
    (net (code "74") (name "SPI_CS_AM") (class "Default")
      (node (ref "H1") (pin "1") (pinfunction "1_1") (pintype "unspecified"))
      (node (ref "U11") (pin "3") (pinfunction "P15_3") (pintype "input"))
      (node (ref "U12") (pin "1") (pinfunction "CS#_1") (pintype "unspecified"))
    )
    (net (code "75") (name "SPI_MISO") (class "Default")
      (node (ref "H1") (pin "2") (pinfunction "2_2") (pintype "unspecified"))
      (node (ref "U11") (pin "1") (pinfunction "P13_1") (pintype "input"))
      (node (ref "U12") (pin "2") (pinfunction "DO（IO1）_2") (pintype "unspecified"))
    )
    (net (code "76") (name "SPI_MOSI") (class "Default")
      (node (ref "H1") (pin "4") (pinfunction "4_4") (pintype "unspecified"))
      (node (ref "U11") (pin "2") (pinfunction "P14_2") (pintype "input"))
      (node (ref "U12") (pin "5") (pinfunction "DI（IO0）_5") (pintype "unspecified"))
    )
    (net (code "77") (name "SPI_SCK") (class "Default")
      (node (ref "H1") (pin "3") (pinfunction "3_3") (pintype "unspecified"))
      (node (ref "U11") (pin "4") (pinfunction "P16_4") (pintype "input"))
      (node (ref "U12") (pin "6") (pinfunction "CLK_6") (pintype "unspecified"))
    )
    (net (code "78") (name "TXD") (class "Default")
      (node (ref "U10") (pin "22") (pinfunction "PB11_22") (pintype "unspecified"))
      (node (ref "U3") (pin "21") (pinfunction "TXD_21") (pintype "unspecified"))
    )
    (net (code "79") (name "USB_DN") (class "Default")
      (node (ref "U3") (pin "4") (pinfunction "D-_4") (pintype "unspecified"))
      (node (ref "USB1") (pin "A7") (pinfunction "DN1_A7") (pintype "input"))
      (node (ref "USB1") (pin "B7") (pinfunction "DN2_B7") (pintype "input"))
    )
    (net (code "80") (name "USB_DP") (class "Default")
      (node (ref "U3") (pin "3") (pinfunction "D+_3") (pintype "unspecified"))
      (node (ref "USB1") (pin "A6") (pinfunction "DP1_A6") (pintype "input"))
      (node (ref "USB1") (pin "B6") (pinfunction "DP2_B6") (pintype "input"))
    )
    (net (code "81") (name "VBAT") (class "Default")
      (node (ref "C13") (pin "1") (pinfunction "1_1") (pintype "input"))
      (node (ref "C15") (pin "2") (pinfunction "2_2") (pintype "input"))
      (node (ref "C16") (pin "2") (pinfunction "2_2") (pintype "input"))
      (node (ref "CN1") (pin "1") (pinfunction "1_1") (pintype "unspecified"))
      (node (ref "U13") (pin "3") (pinfunction "VBAT_3") (pintype "input"))
      (node (ref "U15") (pin "1") (pinfunction "IN_1") (pintype "unspecified"))
      (node (ref "U15") (pin "3") (pinfunction "EN_3") (pintype "unspecified"))
    )
    (net (code "82") (name "VBUS") (class "Default")
      (node (ref "C14") (pin "2") (pinfunction "2_2") (pintype "input"))
      (node (ref "R19") (pin "1") (pinfunction "1_1") (pintype "input"))
      (node (ref "U13") (pin "4") (pinfunction "VDD_4") (pintype "input"))
      (node (ref "U3") (pin "7") (pinfunction "VREGIN_7") (pintype "unspecified"))
      (node (ref "U3") (pin "8") (pinfunction "VBUS_8") (pintype "unspecified"))
      (node (ref "USB1") (pin "A4") (pinfunction "VBUS_A4") (pintype "input"))
      (node (ref "USB1") (pin "A9") (pinfunction "VBUS_A9") (pintype "input"))
      (node (ref "USB1") (pin "B4") (pinfunction "VBUS_B4") (pintype "input"))
      (node (ref "USB1") (pin "B9") (pinfunction "VBUS_B9") (pintype "input"))
    )
    (net (code "83") (name "unconnected-(U3-CTS-Pad18)") (class "Default")
      (node (ref "U3") (pin "18") (pinfunction "CTS_18") (pintype "unspecified+no_connect"))
    )
    (net (code "84") (name "unconnected-(U3-DCD-Pad24)") (class "Default")
      (node (ref "U3") (pin "24") (pinfunction "DCD_24") (pintype "unspecified+no_connect"))
    )
    (net (code "85") (name "unconnected-(U3-DSR-Pad22)") (class "Default")
      (node (ref "U3") (pin "22") (pinfunction "DSR_22") (pintype "unspecified+no_connect"))
    )
    (net (code "86") (name "unconnected-(U3-DTR-Pad23)") (class "Default")
      (node (ref "U3") (pin "23") (pinfunction "DTR_23") (pintype "unspecified+no_connect"))
    )
    (net (code "87") (name "unconnected-(U3-GPIO.0{slash}TXT-Pad14)") (class "Default")
      (node (ref "U3") (pin "14") (pinfunction "GPIO.0/TXT_14") (pintype "unspecified+no_connect"))
    )
    (net (code "88") (name "unconnected-(U3-GPIO.1{slash}RXT-Pad13)") (class "Default")
      (node (ref "U3") (pin "13") (pinfunction "GPIO.1/RXT_13") (pintype "unspecified+no_connect"))
    )
    (net (code "89") (name "unconnected-(U3-GPIO.2{slash}RS485-Pad12)") (class "Default")
      (node (ref "U3") (pin "12") (pinfunction "GPIO.2/RS485_12") (pintype "unspecified+no_connect"))
    )
    (net (code "90") (name "unconnected-(U3-GPIO.3{slash}WAKEUP-Pad11)") (class "Default")
      (node (ref "U3") (pin "11") (pinfunction "GPIO.3/WAKEUP_11") (pintype "unspecified+no_connect"))
    )
    (net (code "91") (name "unconnected-(U3-NC-Pad10)") (class "Default")
      (node (ref "U3") (pin "10") (pinfunction "NC_10") (pintype "unspecified+no_connect"))
    )
    (net (code "92") (name "unconnected-(U3-NC-Pad16)") (class "Default")
      (node (ref "U3") (pin "16") (pinfunction "NC_16") (pintype "unspecified+no_connect"))
    )
    (net (code "93") (name "unconnected-(U3-RI{slash}CLK-Pad1)") (class "Default")
      (node (ref "U3") (pin "1") (pinfunction "RI/CLK_1") (pintype "unspecified+no_connect"))
    )
    (net (code "94") (name "unconnected-(U3-RTS-Pad19)") (class "Default")
      (node (ref "U3") (pin "19") (pinfunction "RTS_19") (pintype "unspecified+no_connect"))
    )
    (net (code "95") (name "unconnected-(U3-SUSPEND-Pad17)") (class "Default")
      (node (ref "U3") (pin "17") (pinfunction "SUSPEND_17") (pintype "unspecified+no_connect"))
    )
    (net (code "96") (name "unconnected-(U3-SUSPENDb-Pad15)") (class "Default")
      (node (ref "U3") (pin "15") (pinfunction "SUSPENDb_15") (pintype "unspecified+no_connect"))
    )
    (net (code "97") (name "unconnected-(U5-NC-Pad3)") (class "Default")
      (node (ref "U5") (pin "3") (pinfunction "NC_3") (pintype "unspecified+no_connect"))
    )
    (net (code "98") (name "unconnected-(U5-NC-Pad4)") (class "Default")
      (node (ref "U5") (pin "4") (pinfunction "NC_4") (pintype "unspecified+no_connect"))
    )
    (net (code "99") (name "unconnected-(U6-n{slash}a-Pad4)") (class "Default")
      (node (ref "U6") (pin "4") (pinfunction "n/a_4") (pintype "unspecified+no_connect"))
    )
    (net (code "100") (name "unconnected-(U10-PC13-TAMPER-RTC-Pad2)") (class "Default")
      (node (ref "U10") (pin "2") (pinfunction "PC13-TAMPER-RTC_2") (pintype "unspecified+no_connect"))
    )
    (net (code "101") (name "unconnected-(U10-PD0-OSCIN-Pad5)") (class "Default")
      (node (ref "U10") (pin "5") (pinfunction "PD0-OSCIN_5") (pintype "unspecified+no_connect"))
    )
    (net (code "102") (name "unconnected-(U10-PD1-OSCOUT-Pad6)") (class "Default")
      (node (ref "U10") (pin "6") (pinfunction "PD1-OSCOUT_6") (pintype "unspecified+no_connect"))
    )
    (net (code "103") (name "unconnected-(U11-NC-Pad20)") (class "Default")
      (node (ref "U11") (pin "20") (pinfunction "NC_20") (pintype "input+no_connect"))
    )
    (net (code "104") (name "unconnected-(U11-P00-Pad6)") (class "Default")
      (node (ref "U11") (pin "6") (pinfunction "P00_6") (pintype "input+no_connect"))
    )
    (net (code "105") (name "unconnected-(U15-NC-Pad4)") (class "Default")
      (node (ref "U15") (pin "4") (pinfunction "NC_4") (pintype "unspecified+no_connect"))
    )
    (net (code "106") (name "unconnected-(USB1-SBUS1-PadA8)") (class "Default")
      (node (ref "USB1") (pin "A8") (pinfunction "SBUS1_A8") (pintype "input+no_connect"))
    )
    (net (code "107") (name "unconnected-(USB1-SBUS2-PadB8)") (class "Default")
      (node (ref "USB1") (pin "B8") (pinfunction "SBUS2_B8") (pintype "input+no_connect"))
    )
  )
)
